# Master_section.net
KiCad netlist of a schematic drawn in EAGLE
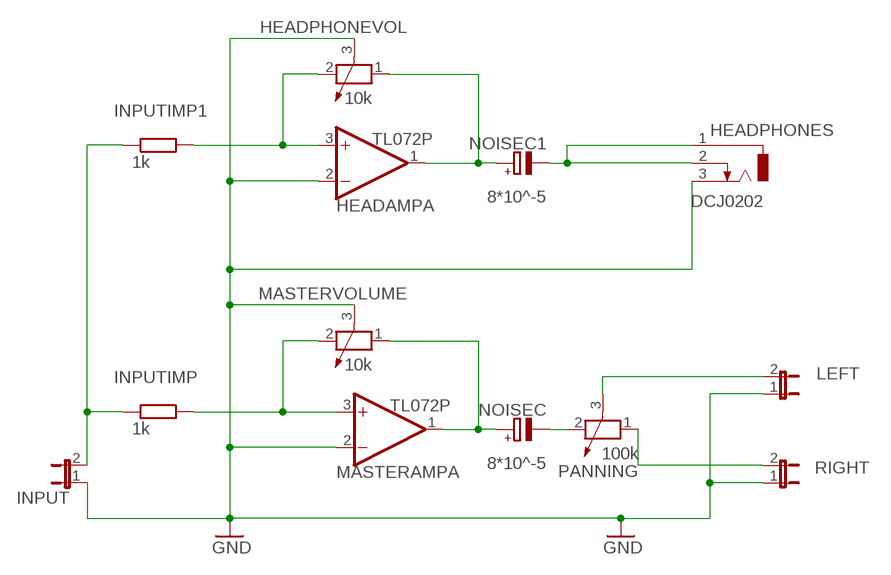
[diagram p0: schematic, sheet 1]

(export (version "E")
  (design (tool "Eeschema 10.0.6"))
  (components
    (comp (ref "HEADAMP")
      (value "TL072P")
      (footprint "eagle-import:DIL08")
      (libsource (lib "eagle-import") (part "TL072P"))
    )
    (comp (ref "HEADPHONES")
      (value "DCJ0202")
      (footprint "eagle-import:DCJ0202")
      (libsource (lib "eagle-import") (part "DCJ0202"))
    )
    (comp (ref "HEADPHONEVOL")
      (value "10k")
      (footprint "eagle-import:PT-10")
      (libsource (lib "eagle-import") (part "POTENTIOMETER_PT-10"))
    )
    (comp (ref "INPUT")
      (value "JP1E")
      (footprint "eagle-import:JP1")
      (libsource (lib "eagle-import") (part "JP1E"))
    )
    (comp (ref "INPUTIMP")
      (value "1k")
      (footprint "eagle-import:0207_7")
      (libsource (lib "eagle-import") (part "R-EU_0207/7"))
    )
    (comp (ref "INPUTIMP1")
      (value "1k")
      (footprint "eagle-import:0207_7")
      (libsource (lib "eagle-import") (part "R-EU_0207/7"))
    )
    (comp (ref "LEFT")
      (value "JP1E")
      (footprint "eagle-import:JP1")
      (libsource (lib "eagle-import") (part "JP1E"))
    )
    (comp (ref "MASTERAMP")
      (value "TL072P")
      (footprint "eagle-import:DIL08")
      (libsource (lib "eagle-import") (part "TL072P"))
    )
    (comp (ref "MASTERVOLUME")
      (value "10k")
      (footprint "eagle-import:PT-10")
      (libsource (lib "eagle-import") (part "POTENTIOMETER_PT-10"))
    )
    (comp (ref "NOISEC")
      (value "8*10^-5")
      (footprint "eagle-import:E5-5")
      (libsource (lib "eagle-import") (part "CPOL-EUE5-5"))
    )
    (comp (ref "NOISEC1")
      (value "8*10^-5")
      (footprint "eagle-import:E5-5")
      (libsource (lib "eagle-import") (part "CPOL-EUE5-5"))
    )
    (comp (ref "PANNING")
      (value "100k")
      (footprint "eagle-import:PT-10")
      (libsource (lib "eagle-import") (part "POTENTIOMETER_PT-10"))
    )
    (comp (ref "RIGHT")
      (value "JP1E")
      (footprint "eagle-import:JP1")
      (libsource (lib "eagle-import") (part "JP1E"))
    )
  )
  (nets
    (net (code "1") (name "GND") (class "Default")
      (node (ref "HEADAMP") (pin "2") (pinfunction "-IN_2") (pintype "input"))
      (node (ref "HEADPHONES") (pin "3") (pinfunction "3_3") (pintype "passive"))
      (node (ref "HEADPHONEVOL") (pin "3") (pinfunction "3_3") (pintype "passive"))
      (node (ref "INPUT") (pin "1") (pinfunction "1_1") (pintype "passive"))
      (node (ref "LEFT") (pin "1") (pinfunction "1_1") (pintype "passive"))
      (node (ref "MASTERAMP") (pin "2") (pinfunction "-IN_2") (pintype "input"))
      (node (ref "MASTERVOLUME") (pin "3") (pinfunction "3_3") (pintype "passive"))
      (node (ref "RIGHT") (pin "1") (pinfunction "1_1") (pintype "passive"))
    )
    (net (code "2") (name "Net-(HEADAMPA-+IN)") (class "Default")
      (node (ref "HEADAMP") (pin "3") (pinfunction "+IN_3") (pintype "input"))
      (node (ref "HEADPHONEVOL") (pin "2") (pinfunction "2_2") (pintype "passive"))
      (node (ref "INPUTIMP1") (pin "2") (pinfunction "2_2") (pintype "passive"))
    )
    (net (code "3") (name "Net-(HEADAMPA-OUT)") (class "Default")
      (node (ref "HEADAMP") (pin "1") (pinfunction "OUT_1") (pintype "output"))
      (node (ref "HEADPHONEVOL") (pin "1") (pinfunction "1_1") (pintype "passive"))
      (node (ref "NOISEC1") (pin "+") (pinfunction "+_+") (pintype "passive"))
    )
    (net (code "4") (name "Net-(HEADPHONES-Pad1)") (class "Default")
      (node (ref "HEADPHONES") (pin "1") (pinfunction "1_1") (pintype "passive"))
      (node (ref "HEADPHONES") (pin "2") (pinfunction "2_2") (pintype "passive"))
      (node (ref "NOISEC1") (pin "-") (pinfunction "-_-") (pintype "passive"))
    )
    (net (code "5") (name "Net-(INPUT-Pad2)") (class "Default")
      (node (ref "INPUT") (pin "2") (pinfunction "2_2") (pintype "passive"))
      (node (ref "INPUTIMP") (pin "1") (pinfunction "1_1") (pintype "passive"))
      (node (ref "INPUTIMP1") (pin "1") (pinfunction "1_1") (pintype "passive"))
    )
    (net (code "6") (name "Net-(LEFT-Pad2)") (class "Default")
      (node (ref "LEFT") (pin "2") (pinfunction "2_2") (pintype "passive"))
      (node (ref "PANNING") (pin "3") (pinfunction "3_3") (pintype "passive"))
    )
    (net (code "7") (name "Net-(MASTERAMPA-+IN)") (class "Default")
      (node (ref "INPUTIMP") (pin "2") (pinfunction "2_2") (pintype "passive"))
      (node (ref "MASTERAMP") (pin "3") (pinfunction "+IN_3") (pintype "input"))
      (node (ref "MASTERVOLUME") (pin "2") (pinfunction "2_2") (pintype "passive"))
    )
    (net (code "8") (name "Net-(MASTERAMPA-OUT)") (class "Default")
      (node (ref "MASTERAMP") (pin "1") (pinfunction "OUT_1") (pintype "output"))
      (node (ref "MASTERVOLUME") (pin "1") (pinfunction "1_1") (pintype "passive"))
      (node (ref "NOISEC") (pin "+") (pinfunction "+_+") (pintype "passive"))
    )
    (net (code "9") (name "Net-(NOISEC-Pad-)") (class "Default")
      (node (ref "NOISEC") (pin "-") (pinfunction "-_-") (pintype "passive"))
      (node (ref "PANNING") (pin "2") (pinfunction "2_2") (pintype "passive"))
    )
    (net (code "10") (name "Net-(PANNING-Pad1)") (class "Default")
      (node (ref "PANNING") (pin "1") (pinfunction "1_1") (pintype "passive"))
      (node (ref "RIGHT") (pin "2") (pinfunction "2_2") (pintype "passive"))
    )
  )
)
